# MCU.net
KiCad netlist of a schematic drawn in Altium Designer
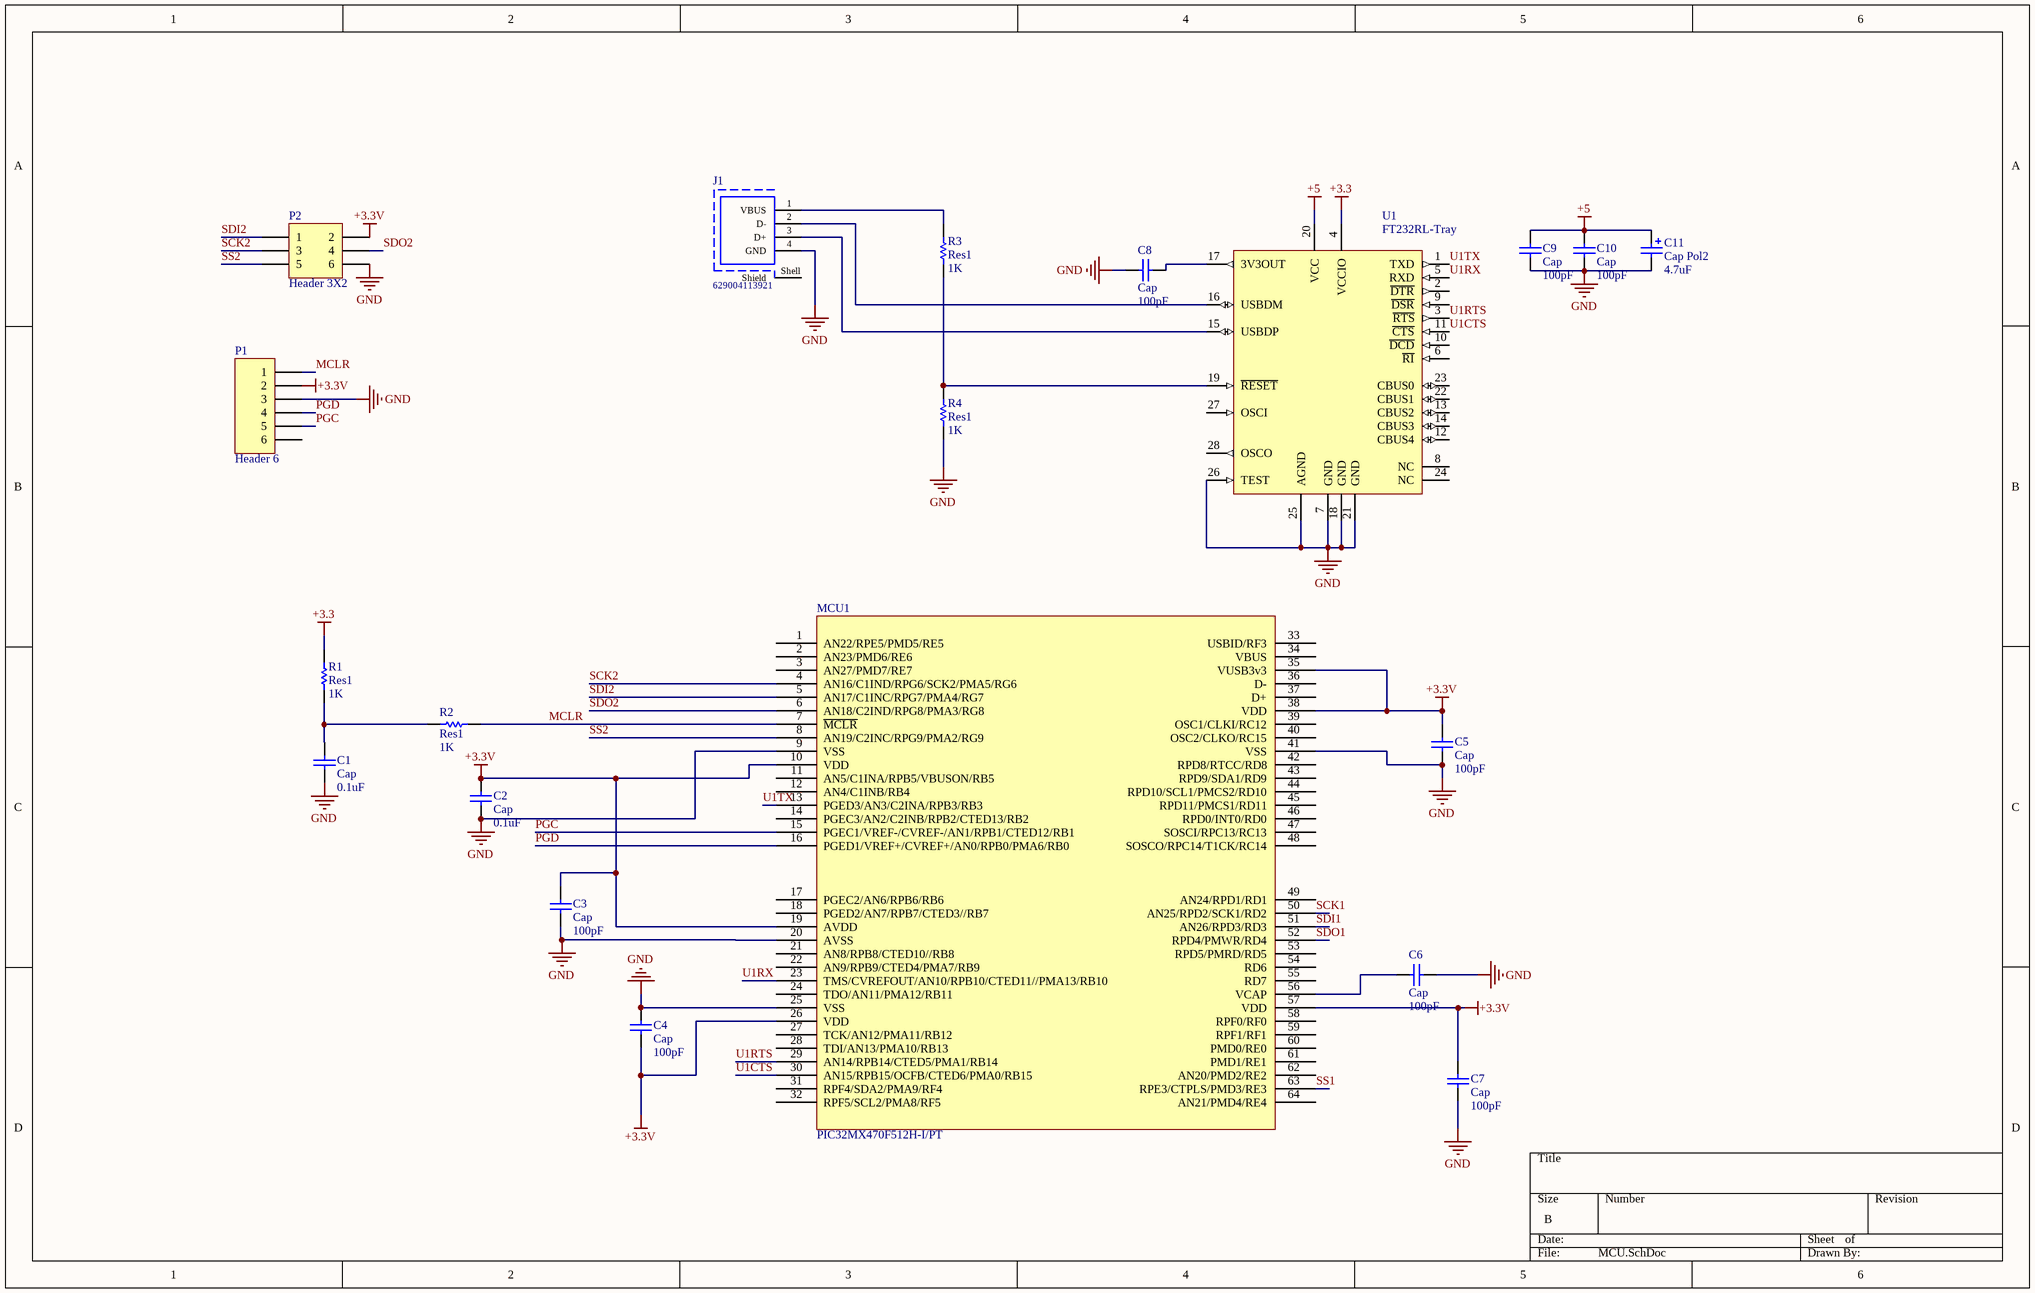
[diagram p0: MCU.SchDoc]

(export (version "E")
  (design (tool "Eeschema 10.0.6"))
  (components
    (comp (ref "C1")
      (value "Cap")
      (footprint "RAD-0.3")
      (description "Capacitor")
      (fields (field (name "ALTIUM_VALUE") "0.1uF") (field (name "PUBLISHER") "Altium Limited"))
      (libsource (lib "Miscellaneous Devices") (part "Cap"))
    )
    (comp (ref "C2")
      (value "Cap")
      (footprint "RAD-0.3")
      (description "Capacitor")
      (fields (field (name "ALTIUM_VALUE") "0.1uF") (field (name "PUBLISHER") "Altium Limited"))
      (libsource (lib "Miscellaneous Devices") (part "Cap"))
    )
    (comp (ref "C3")
      (value "Cap")
      (footprint "RAD-0.3")
      (description "Capacitor")
      (fields (field (name "ALTIUM_VALUE") "100pF") (field (name "PUBLISHER") "Altium Limited"))
      (libsource (lib "Miscellaneous Devices") (part "Cap"))
    )
    (comp (ref "C4")
      (value "Cap")
      (footprint "RAD-0.3")
      (description "Capacitor")
      (fields (field (name "ALTIUM_VALUE") "100pF") (field (name "PUBLISHER") "Altium Limited"))
      (libsource (lib "Miscellaneous Devices") (part "Cap"))
    )
    (comp (ref "C5")
      (value "Cap")
      (footprint "RAD-0.3")
      (description "Capacitor")
      (fields (field (name "ALTIUM_VALUE") "100pF") (field (name "PUBLISHER") "Altium Limited"))
      (libsource (lib "Miscellaneous Devices") (part "Cap"))
    )
    (comp (ref "C6")
      (value "Cap")
      (footprint "RAD-0.3")
      (description "Capacitor")
      (fields (field (name "ALTIUM_VALUE") "100pF") (field (name "PUBLISHER") "Altium Limited"))
      (libsource (lib "Miscellaneous Devices") (part "Cap"))
    )
    (comp (ref "C7")
      (value "Cap")
      (footprint "RAD-0.3")
      (description "Capacitor")
      (fields (field (name "ALTIUM_VALUE") "100pF") (field (name "PUBLISHER") "Altium Limited"))
      (libsource (lib "Miscellaneous Devices") (part "Cap"))
    )
    (comp (ref "C8")
      (value "Cap")
      (footprint "RAD-0.3")
      (description "Capacitor")
      (fields (field (name "ALTIUM_VALUE") "100pF") (field (name "PUBLISHER") "Altium Limited"))
      (libsource (lib "Miscellaneous Devices") (part "Cap"))
    )
    (comp (ref "C9")
      (value "Cap")
      (footprint "RAD-0.3")
      (description "Capacitor")
      (fields (field (name "ALTIUM_VALUE") "100pF") (field (name "PUBLISHER") "Altium Limited"))
      (libsource (lib "Miscellaneous Devices") (part "Cap"))
    )
    (comp (ref "C10")
      (value "Cap")
      (footprint "RAD-0.3")
      (description "Capacitor")
      (fields (field (name "ALTIUM_VALUE") "100pF") (field (name "PUBLISHER") "Altium Limited"))
      (libsource (lib "Miscellaneous Devices") (part "Cap"))
    )
    (comp (ref "C11")
      (value "Cap Pol2")
      (footprint "POLAR0.8")
      (description "Polarized Capacitor (Axial)")
      (fields (field (name "ALTIUM_VALUE") "4.7uF") (field (name "PUBLISHER") "Altium Limited"))
      (libsource (lib "Miscellaneous Devices") (part "Cap Pol2"))
    )
    (comp (ref "J1")
      (value "629004113921")
      (footprint "629004113921")
      (description "USB 2.0 Type A Plug WR-COM, Horizontal, SMT, with Clips")
      (fields (field (name "MANUFACTURER") "Wurth Elektronik") (field (name "PUBLISHER") "WurthElektronik"))
      (libsource (lib "Altium Content Vault") (part "WE-USB-4-1SHLD"))
    )
    (comp (ref "MCU1")
      (value "PIC32MX470F512H-I/PT")
      (footprint "*QFP50P1200X1200X120-64N")
      (libsource (lib "MINTCustom") (part "PIC32MX470F512H-I/PT"))
    )
    (comp (ref "P1")
      (value "Header 6")
      (footprint "HDR1X6")
      (description "Header, 6-Pin")
      (fields (field (name "PUBLISHER") "Altium Limited"))
      (libsource (lib "Miscellaneous Connectors") (part "Header 6"))
    )
    (comp (ref "P2")
      (value "Header 3X2")
      (footprint "HDR2X3")
      (description "Header, 3-Pin, Dual row")
      (fields (field (name "PUBLISHER") "Altium Limited"))
      (libsource (lib "Miscellaneous Connectors") (part "Header 3X2"))
    )
    (comp (ref "R1")
      (value "Res1")
      (footprint "AXIAL-0.3")
      (description "Resistor")
      (fields (field (name "ALTIUM_VALUE") "1K") (field (name "PUBLISHER") "Altium Limited"))
      (libsource (lib "Miscellaneous Devices") (part "Res1"))
    )
    (comp (ref "R2")
      (value "Res1")
      (footprint "AXIAL-0.3")
      (description "Resistor")
      (fields (field (name "ALTIUM_VALUE") "1K") (field (name "PUBLISHER") "Altium Limited"))
      (libsource (lib "Miscellaneous Devices") (part "Res1"))
    )
    (comp (ref "R3")
      (value "Res1")
      (footprint "AXIAL-0.3")
      (description "Resistor")
      (fields (field (name "ALTIUM_VALUE") "1K") (field (name "PUBLISHER") "Altium Limited"))
      (libsource (lib "Miscellaneous Devices") (part "Res1"))
    )
    (comp (ref "R4")
      (value "Res1")
      (footprint "AXIAL-0.3")
      (description "Resistor")
      (fields (field (name "ALTIUM_VALUE") "1K") (field (name "PUBLISHER") "Altium Limited"))
      (libsource (lib "Miscellaneous Devices") (part "Res1"))
    )
    (comp (ref "U1")
      (value "FT232RL-Tray")
      (footprint "SSOP-28_L")
      (description "USB UART Asynchronous Serial Data Transfer Chip, SSOP-28, Tray")
      (libsource (lib "Altium Content Vault") (part "COM-UART-FT232R-IL28"))
    )
  )
  (nets
    (net (code "1") (name "+3.3") (class "Default")
      (node (ref "R1") (pin "2") (pinfunction "2_2") (pintype "passive"))
      (node (ref "U1") (pin "4") (pinfunction "VCCIO_4") (pintype "power_in"))
    )
    (net (code "2") (name "+3.3V") (class "Default")
      (node (ref "C2") (pin "2") (pinfunction "2_2") (pintype "passive"))
      (node (ref "C3") (pin "2") (pinfunction "2_2") (pintype "passive"))
      (node (ref "C4") (pin "2") (pinfunction "2_2") (pintype "passive"))
      (node (ref "C5") (pin "2") (pinfunction "2_2") (pintype "passive"))
      (node (ref "C7") (pin "1") (pinfunction "1_1") (pintype "passive"))
      (node (ref "MCU1") (pin "10") (pinfunction "VDD_10") (pintype "passive"))
      (node (ref "MCU1") (pin "19") (pinfunction "AVDD_19") (pintype "passive"))
      (node (ref "MCU1") (pin "26") (pinfunction "VDD_26") (pintype "passive"))
      (node (ref "MCU1") (pin "35") (pinfunction "VUSB3v3_35") (pintype "passive"))
      (node (ref "MCU1") (pin "38") (pinfunction "VDD_38") (pintype "passive"))
      (node (ref "MCU1") (pin "57") (pinfunction "VDD_57") (pintype "passive"))
      (node (ref "P1") (pin "2") (pinfunction "2_2") (pintype "passive"))
      (node (ref "P2") (pin "2") (pinfunction "2_2") (pintype "passive"))
    )
    (net (code "3") (name "+5") (class "Default")
      (node (ref "C10") (pin "2") (pinfunction "2_2") (pintype "passive"))
      (node (ref "C11") (pin "1") (pinfunction "1_1") (pintype "passive"))
      (node (ref "C9") (pin "2") (pinfunction "2_2") (pintype "passive"))
      (node (ref "U1") (pin "20") (pinfunction "VCC_20") (pintype "power_in"))
    )
    (net (code "4") (name "/MCLR") (class "Default")
      (node (ref "MCU1") (pin "7") (pinfunction "~{MCLR}_7") (pintype "passive"))
      (node (ref "P1") (pin "1") (pinfunction "1_1") (pintype "passive"))
      (node (ref "R2") (pin "1") (pinfunction "1_1") (pintype "passive"))
    )
    (net (code "5") (name "/PGC") (class "Default")
      (node (ref "MCU1") (pin "15") (pinfunction "PGEC1/VREF-/CVREF-/AN1/RPB1/CTED12/RB1_15") (pintype "passive"))
      (node (ref "P1") (pin "5") (pinfunction "5_5") (pintype "passive"))
    )
    (net (code "6") (name "/PGD") (class "Default")
      (node (ref "MCU1") (pin "16") (pinfunction "PGED1/VREF+/CVREF+/AN0/RPB0/PMA6/RB0_16") (pintype "passive"))
      (node (ref "P1") (pin "4") (pinfunction "4_4") (pintype "passive"))
    )
    (net (code "7") (name "/SCK1") (class "Default")
      (node (ref "MCU1") (pin "50") (pinfunction "AN25/RPD2/SCK1/RD2_50") (pintype "passive"))
    )
    (net (code "8") (name "/SCK2") (class "Default")
      (node (ref "MCU1") (pin "4") (pinfunction "AN16/C1IND/RPG6/SCK2/PMA5/RG6_4") (pintype "passive"))
      (node (ref "P2") (pin "3") (pinfunction "3_3") (pintype "passive"))
    )
    (net (code "9") (name "/SDI1") (class "Default")
      (node (ref "MCU1") (pin "51") (pinfunction "AN26/RPD3/RD3_51") (pintype "passive"))
    )
    (net (code "10") (name "/SDI2") (class "Default")
      (node (ref "MCU1") (pin "5") (pinfunction "AN17/C1INC/RPG7/PMA4/RG7_5") (pintype "passive"))
      (node (ref "P2") (pin "1") (pinfunction "1_1") (pintype "passive"))
    )
    (net (code "11") (name "/SDO1") (class "Default")
      (node (ref "MCU1") (pin "52") (pinfunction "RPD4/PMWR/RD4_52") (pintype "passive"))
    )
    (net (code "12") (name "/SDO2") (class "Default")
      (node (ref "MCU1") (pin "6") (pinfunction "AN18/C2IND/RPG8/PMA3/RG8_6") (pintype "passive"))
      (node (ref "P2") (pin "4") (pinfunction "4_4") (pintype "passive"))
    )
    (net (code "13") (name "/SS1") (class "Default")
      (node (ref "MCU1") (pin "63") (pinfunction "RPE3/CTPLS/PMD3/RE3_63") (pintype "passive"))
    )
    (net (code "14") (name "/SS2") (class "Default")
      (node (ref "MCU1") (pin "8") (pinfunction "AN19/C2INC/RPG9/PMA2/RG9_8") (pintype "passive"))
      (node (ref "P2") (pin "5") (pinfunction "5_5") (pintype "passive"))
    )
    (net (code "15") (name "/U1CTS") (class "Default")
      (node (ref "MCU1") (pin "30") (pinfunction "AN15/RPB15/OCFB/CTED6/PMA0/RB15_30") (pintype "passive"))
      (node (ref "U1") (pin "11") (pinfunction "~{CTS}_11") (pintype "input"))
    )
    (net (code "16") (name "/U1RTS") (class "Default")
      (node (ref "MCU1") (pin "29") (pinfunction "AN14/RPB14/CTED5/PMA1/RB14_29") (pintype "passive"))
      (node (ref "U1") (pin "3") (pinfunction "~{RTS}_3") (pintype "output"))
    )
    (net (code "17") (name "/U1RX") (class "Default")
      (node (ref "MCU1") (pin "23") (pinfunction "TMS/CVREFOUT/AN10/RPB10/CTED11//PMA13/RB10_23") (pintype "passive"))
      (node (ref "U1") (pin "5") (pinfunction "RXD_5") (pintype "input"))
    )
    (net (code "18") (name "/U1TX") (class "Default")
      (node (ref "MCU1") (pin "13") (pinfunction "PGED3/AN3/C2INA/RPB3/RB3_13") (pintype "passive"))
      (node (ref "U1") (pin "1") (pinfunction "TXD_1") (pintype "output"))
    )
    (net (code "19") (name "GND") (class "Default")
      (node (ref "C1") (pin "1") (pinfunction "1_1") (pintype "passive"))
      (node (ref "C10") (pin "1") (pinfunction "1_1") (pintype "passive"))
      (node (ref "C11") (pin "2") (pinfunction "2_2") (pintype "passive"))
      (node (ref "C2") (pin "1") (pinfunction "1_1") (pintype "passive"))
      (node (ref "C3") (pin "1") (pinfunction "1_1") (pintype "passive"))
      (node (ref "C4") (pin "1") (pinfunction "1_1") (pintype "passive"))
      (node (ref "C5") (pin "1") (pinfunction "1_1") (pintype "passive"))
      (node (ref "C6") (pin "2") (pinfunction "2_2") (pintype "passive"))
      (node (ref "C7") (pin "2") (pinfunction "2_2") (pintype "passive"))
      (node (ref "C8") (pin "1") (pinfunction "1_1") (pintype "passive"))
      (node (ref "C9") (pin "1") (pinfunction "1_1") (pintype "passive"))
      (node (ref "J1") (pin "4") (pinfunction "GND_4") (pintype "passive"))
      (node (ref "MCU1") (pin "20") (pinfunction "AVSS_20") (pintype "passive"))
      (node (ref "MCU1") (pin "25") (pinfunction "VSS_25") (pintype "passive"))
      (node (ref "MCU1") (pin "41") (pinfunction "VSS_41") (pintype "passive"))
      (node (ref "MCU1") (pin "9") (pinfunction "VSS_9") (pintype "passive"))
      (node (ref "P1") (pin "3") (pinfunction "3_3") (pintype "passive"))
      (node (ref "P2") (pin "6") (pinfunction "6_6") (pintype "passive"))
      (node (ref "R4") (pin "2") (pinfunction "2_2") (pintype "passive"))
      (node (ref "U1") (pin "18") (pinfunction "GND_18") (pintype "power_in"))
      (node (ref "U1") (pin "21") (pinfunction "GND_21") (pintype "power_in"))
      (node (ref "U1") (pin "25") (pinfunction "AGND_25") (pintype "power_in"))
      (node (ref "U1") (pin "26") (pinfunction "TEST_26") (pintype "input"))
      (node (ref "U1") (pin "7") (pinfunction "GND_7") (pintype "power_in"))
    )
    (net (code "20") (name "Net-(C1-Pad2)") (class "Default")
      (node (ref "C1") (pin "2") (pinfunction "2_2") (pintype "passive"))
      (node (ref "R1") (pin "1") (pinfunction "1_1") (pintype "passive"))
      (node (ref "R2") (pin "2") (pinfunction "2_2") (pintype "passive"))
    )
    (net (code "21") (name "Net-(J1-D+)") (class "Default")
      (node (ref "J1") (pin "3") (pinfunction "D+_3") (pintype "passive"))
      (node (ref "U1") (pin "15") (pinfunction "USBDP_15") (pintype "bidirectional"))
    )
    (net (code "22") (name "Net-(J1-D-)") (class "Default")
      (node (ref "J1") (pin "2") (pinfunction "D-_2") (pintype "passive"))
      (node (ref "U1") (pin "16") (pinfunction "USBDM_16") (pintype "bidirectional"))
    )
    (net (code "23") (name "Net-(J1-VBUS)") (class "Default")
      (node (ref "J1") (pin "1") (pinfunction "VBUS_1") (pintype "passive"))
      (node (ref "R3") (pin "1") (pinfunction "1_1") (pintype "passive"))
    )
    (net (code "24") (name "Net-(MCU1-VCAP)") (class "Default")
      (node (ref "C6") (pin "1") (pinfunction "1_1") (pintype "passive"))
      (node (ref "MCU1") (pin "56") (pinfunction "VCAP_56") (pintype "passive"))
    )
    (net (code "25") (name "Net-(U1-3V3OUT)") (class "Default")
      (node (ref "C8") (pin "2") (pinfunction "2_2") (pintype "passive"))
      (node (ref "U1") (pin "17") (pinfunction "3V3OUT_17") (pintype "output"))
    )
    (net (code "26") (name "Net-(U1-~{RESET})") (class "Default")
      (node (ref "R3") (pin "2") (pinfunction "2_2") (pintype "passive"))
      (node (ref "R4") (pin "1") (pinfunction "1_1") (pintype "passive"))
      (node (ref "U1") (pin "19") (pinfunction "~{RESET}_19") (pintype "input"))
    )
    (net (code "27") (name "unconnected-(J1-Shield-PadShell)") (class "Default")
      (node (ref "J1") (pin "Shell") (pinfunction "Shield_Shell") (pintype "passive"))
    )
    (net (code "28") (name "unconnected-(MCU1-AN4{slash}C1INB{slash}RB4-Pad12)") (class "Default")
      (node (ref "MCU1") (pin "12") (pinfunction "AN4/C1INB/RB4_12") (pintype "passive"))
    )
    (net (code "29") (name "unconnected-(MCU1-AN5{slash}C1INA{slash}RPB5{slash}VBUSON{slash}RB5-Pad11)") (class "Default")
      (node (ref "MCU1") (pin "11") (pinfunction "AN5/C1INA/RPB5/VBUSON/RB5_11") (pintype "passive"))
    )
    (net (code "30") (name "unconnected-(MCU1-AN8{slash}RPB8{slash}CTED10{slash}{slash}RB8-Pad21)") (class "Default")
      (node (ref "MCU1") (pin "21") (pinfunction "AN8/RPB8/CTED10//RB8_21") (pintype "passive"))
    )
    (net (code "31") (name "unconnected-(MCU1-AN9{slash}RPB9{slash}CTED4{slash}PMA7{slash}RB9-Pad22)") (class "Default")
      (node (ref "MCU1") (pin "22") (pinfunction "AN9/RPB9/CTED4/PMA7/RB9_22") (pintype "passive"))
    )
    (net (code "32") (name "unconnected-(MCU1-AN20{slash}PMD2{slash}RE2-Pad62)") (class "Default")
      (node (ref "MCU1") (pin "62") (pinfunction "AN20/PMD2/RE2_62") (pintype "passive"))
    )
    (net (code "33") (name "unconnected-(MCU1-AN21{slash}PMD4{slash}RE4-Pad64)") (class "Default")
      (node (ref "MCU1") (pin "64") (pinfunction "AN21/PMD4/RE4_64") (pintype "passive"))
    )
    (net (code "34") (name "unconnected-(MCU1-AN22{slash}RPE5{slash}PMD5{slash}RE5-Pad1)") (class "Default")
      (node (ref "MCU1") (pin "1") (pinfunction "AN22/RPE5/PMD5/RE5_1") (pintype "passive"))
    )
    (net (code "35") (name "unconnected-(MCU1-AN23{slash}PMD6{slash}RE6-Pad2)") (class "Default")
      (node (ref "MCU1") (pin "2") (pinfunction "AN23/PMD6/RE6_2") (pintype "passive"))
    )
    (net (code "36") (name "unconnected-(MCU1-AN27{slash}PMD7{slash}RE7-Pad3)") (class "Default")
      (node (ref "MCU1") (pin "3") (pinfunction "AN27/PMD7/RE7_3") (pintype "passive"))
    )
    (net (code "37") (name "unconnected-(MCU1-D+-Pad37)") (class "Default")
      (node (ref "MCU1") (pin "37") (pinfunction "D+_37") (pintype "passive"))
    )
    (net (code "38") (name "unconnected-(MCU1-D--Pad36)") (class "Default")
      (node (ref "MCU1") (pin "36") (pinfunction "D-_36") (pintype "passive"))
    )
    (net (code "39") (name "unconnected-(MCU1-OSC1{slash}CLKI{slash}RC12-Pad39)") (class "Default")
      (node (ref "MCU1") (pin "39") (pinfunction "OSC1/CLKI/RC12_39") (pintype "passive"))
    )
    (net (code "40") (name "unconnected-(MCU1-OSC2{slash}CLKO{slash}RC15-Pad40)") (class "Default")
      (node (ref "MCU1") (pin "40") (pinfunction "OSC2/CLKO/RC15_40") (pintype "passive"))
    )
    (net (code "41") (name "unconnected-(MCU1-PGEC2{slash}AN6{slash}RPB6{slash}RB6-Pad17)") (class "Default")
      (node (ref "MCU1") (pin "17") (pinfunction "PGEC2/AN6/RPB6/RB6_17") (pintype "passive"))
    )
    (net (code "42") (name "unconnected-(MCU1-PGEC3{slash}AN2{slash}C2INB{slash}RPB2{slash}CTED13{slash}RB2-Pad14)") (class "Default")
      (node (ref "MCU1") (pin "14") (pinfunction "PGEC3/AN2/C2INB/RPB2/CTED13/RB2_14") (pintype "passive"))
    )
    (net (code "43") (name "unconnected-(MCU1-PGED2{slash}AN7{slash}RPB7{slash}CTED3{slash}{slash}RB7-Pad18)") (class "Default")
      (node (ref "MCU1") (pin "18") (pinfunction "PGED2/AN7/RPB7/CTED3//RB7_18") (pintype "passive"))
    )
    (net (code "44") (name "unconnected-(MCU1-PMD0{slash}RE0-Pad60)") (class "Default")
      (node (ref "MCU1") (pin "60") (pinfunction "PMD0/RE0_60") (pintype "passive"))
    )
    (net (code "45") (name "unconnected-(MCU1-PMD1{slash}RE1-Pad61)") (class "Default")
      (node (ref "MCU1") (pin "61") (pinfunction "PMD1/RE1_61") (pintype "passive"))
    )
    (net (code "46") (name "unconnected-(MCU1-RD6-Pad54)") (class "Default")
      (node (ref "MCU1") (pin "54") (pinfunction "RD6_54") (pintype "passive"))
    )
    (net (code "47") (name "unconnected-(MCU1-RD7-Pad55)") (class "Default")
      (node (ref "MCU1") (pin "55") (pinfunction "RD7_55") (pintype "passive"))
    )
    (net (code "48") (name "unconnected-(MCU1-RPD0{slash}INT0{slash}RD0-Pad46)") (class "Default")
      (node (ref "MCU1") (pin "46") (pinfunction "RPD0/INT0/RD0_46") (pintype "passive"))
    )
    (net (code "49") (name "unconnected-(MCU1-RPD5{slash}PMRD{slash}RD5-Pad53)") (class "Default")
      (node (ref "MCU1") (pin "53") (pinfunction "RPD5/PMRD/RD5_53") (pintype "passive"))
    )
    (net (code "50") (name "unconnected-(MCU1-RPD8{slash}RTCC{slash}RD8-Pad42)") (class "Default")
      (node (ref "MCU1") (pin "42") (pinfunction "RPD8/RTCC/RD8_42") (pintype "passive"))
    )
    (net (code "51") (name "unconnected-(MCU1-RPD9{slash}SDA1{slash}RD9-Pad43)") (class "Default")
      (node (ref "MCU1") (pin "43") (pinfunction "RPD9/SDA1/RD9_43") (pintype "passive"))
    )
    (net (code "52") (name "unconnected-(MCU1-RPD11{slash}PMCS1{slash}RD11-Pad45)") (class "Default")
      (node (ref "MCU1") (pin "45") (pinfunction "RPD11/PMCS1/RD11_45") (pintype "passive"))
    )
    (net (code "53") (name "unconnected-(MCU1-RPF1{slash}RF1-Pad59)") (class "Default")
      (node (ref "MCU1") (pin "59") (pinfunction "RPF1/RF1_59") (pintype "passive"))
    )
    (net (code "54") (name "unconnected-(MCU1-RPF4{slash}SDA2{slash}PMA9{slash}RF4-Pad31)") (class "Default")
      (node (ref "MCU1") (pin "31") (pinfunction "RPF4/SDA2/PMA9/RF4_31") (pintype "passive"))
    )
    (net (code "55") (name "unconnected-(MCU1-RPF5{slash}SCL2{slash}PMA8{slash}RF5-Pad32)") (class "Default")
      (node (ref "MCU1") (pin "32") (pinfunction "RPF5/SCL2/PMA8/RF5_32") (pintype "passive"))
    )
    (net (code "56") (name "unconnected-(MCU1-SOSCI{slash}RPC13{slash}RC13-Pad47)") (class "Default")
      (node (ref "MCU1") (pin "47") (pinfunction "SOSCI/RPC13/RC13_47") (pintype "passive"))
    )
    (net (code "57") (name "unconnected-(MCU1-SOSCO{slash}RPC14{slash}T1CK{slash}RC14-Pad48)") (class "Default")
      (node (ref "MCU1") (pin "48") (pinfunction "SOSCO/RPC14/T1CK/RC14_48") (pintype "passive"))
    )
    (net (code "58") (name "unconnected-(MCU1-TCK{slash}AN12{slash}PMA11{slash}RB12-Pad27)") (class "Default")
      (node (ref "MCU1") (pin "27") (pinfunction "TCK/AN12/PMA11/RB12_27") (pintype "passive"))
    )
    (net (code "59") (name "unconnected-(MCU1-TDI{slash}AN13{slash}PMA10{slash}RB13-Pad28)") (class "Default")
      (node (ref "MCU1") (pin "28") (pinfunction "TDI/AN13/PMA10/RB13_28") (pintype "passive"))
    )
    (net (code "60") (name "unconnected-(MCU1-TDO{slash}AN11{slash}PMA12{slash}RB11-Pad24)") (class "Default")
      (node (ref "MCU1") (pin "24") (pinfunction "TDO/AN11/PMA12/RB11_24") (pintype "passive"))
    )
    (net (code "61") (name "unconnected-(MCU1-USBID{slash}RF3-Pad33)") (class "Default")
      (node (ref "MCU1") (pin "33") (pinfunction "USBID/RF3_33") (pintype "passive"))
    )
    (net (code "62") (name "unconnected-(MCU1-VBUS-Pad34)") (class "Default")
      (node (ref "MCU1") (pin "34") (pinfunction "VBUS_34") (pintype "passive"))
    )
    (net (code "63") (name "unconnected-(MCU1-_AN24{slash}RPD1{slash}RD1-Pad49)") (class "Default")
      (node (ref "MCU1") (pin "49") (pinfunction "_AN24/RPD1/RD1_49") (pintype "passive"))
    )
    (net (code "64") (name "unconnected-(MCU1-_RPD10{slash}SCL1{slash}PMCS2{slash}RD10-Pad44)") (class "Default")
      (node (ref "MCU1") (pin "44") (pinfunction "_RPD10/SCL1/PMCS2/RD10_44") (pintype "passive"))
    )
    (net (code "65") (name "unconnected-(MCU1-_RPF0{slash}RF0-Pad58)") (class "Default")
      (node (ref "MCU1") (pin "58") (pinfunction "_RPF0/RF0_58") (pintype "passive"))
    )
    (net (code "66") (name "unconnected-(P1-Pad6)") (class "Default")
      (node (ref "P1") (pin "6") (pinfunction "6_6") (pintype "passive"))
    )
    (net (code "67") (name "unconnected-(U1-CBUS0-Pad23)") (class "Default")
      (node (ref "U1") (pin "23") (pinfunction "CBUS0_23") (pintype "bidirectional"))
    )
    (net (code "68") (name "unconnected-(U1-CBUS1-Pad22)") (class "Default")
      (node (ref "U1") (pin "22") (pinfunction "CBUS1_22") (pintype "bidirectional"))
    )
    (net (code "69") (name "unconnected-(U1-CBUS2-Pad13)") (class "Default")
      (node (ref "U1") (pin "13") (pinfunction "CBUS2_13") (pintype "bidirectional"))
    )
    (net (code "70") (name "unconnected-(U1-CBUS3-Pad14)") (class "Default")
      (node (ref "U1") (pin "14") (pinfunction "CBUS3_14") (pintype "bidirectional"))
    )
    (net (code "71") (name "unconnected-(U1-CBUS4-Pad12)") (class "Default")
      (node (ref "U1") (pin "12") (pinfunction "CBUS4_12") (pintype "bidirectional"))
    )
    (net (code "72") (name "unconnected-(U1-NC-Pad8)") (class "Default")
      (node (ref "U1") (pin "8") (pinfunction "NC_8") (pintype "passive"))
    )
    (net (code "73") (name "unconnected-(U1-NC-Pad24)") (class "Default")
      (node (ref "U1") (pin "24") (pinfunction "NC_24") (pintype "passive"))
    )
    (net (code "74") (name "unconnected-(U1-OSCI-Pad27)") (class "Default")
      (node (ref "U1") (pin "27") (pinfunction "OSCI_27") (pintype "input"))
    )
    (net (code "75") (name "unconnected-(U1-OSCO-Pad28)") (class "Default")
      (node (ref "U1") (pin "28") (pinfunction "OSCO_28") (pintype "output"))
    )
    (net (code "76") (name "unconnected-(U1-~{DCD}-Pad10)") (class "Default")
      (node (ref "U1") (pin "10") (pinfunction "~{DCD}_10") (pintype "input"))
    )
    (net (code "77") (name "unconnected-(U1-~{DSR}-Pad9)") (class "Default")
      (node (ref "U1") (pin "9") (pinfunction "~{DSR}_9") (pintype "input"))
    )
    (net (code "78") (name "unconnected-(U1-~{DTR}-Pad2)") (class "Default")
      (node (ref "U1") (pin "2") (pinfunction "~{DTR}_2") (pintype "output"))
    )
    (net (code "79") (name "unconnected-(U1-~{RI}-Pad6)") (class "Default")
      (node (ref "U1") (pin "6") (pinfunction "~{RI}_6") (pintype "input"))
    )
  )
)
